# Power.net
KiCad netlist of a schematic drawn in Altium Designer
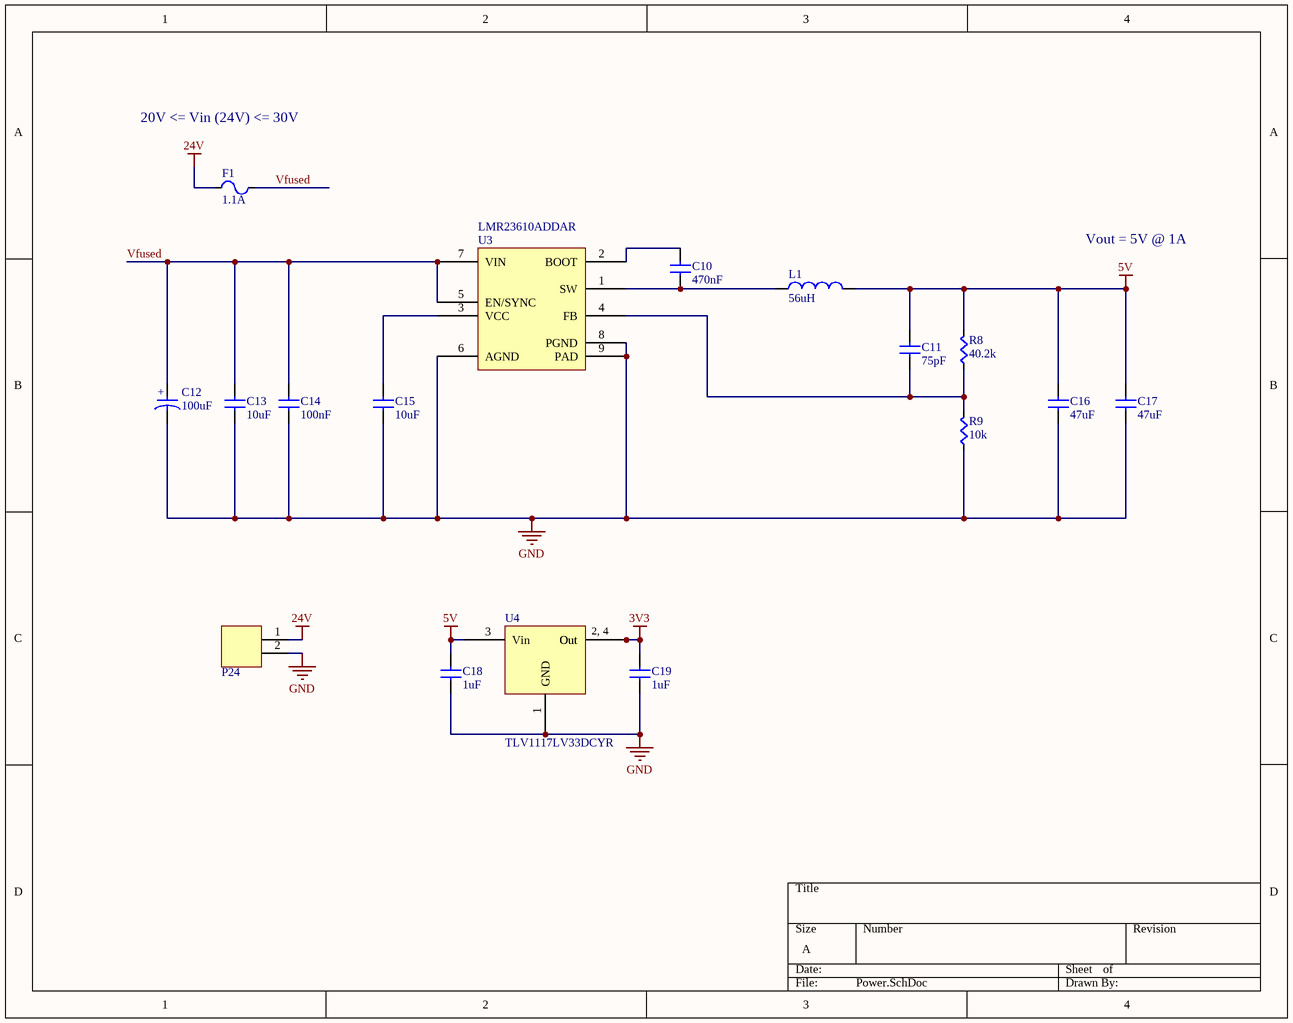
[diagram p0: Power.SchDoc]

(export (version "E")
  (design (tool "Eeschema 10.0.6"))
  (components
    (comp (ref "C10")
      (value "470nF")
      (footprint "CAPC0603")
      (fields (field (name "Comment") "Cap"))
      (libsource (lib "Passives") (part "Cap"))
    )
    (comp (ref "C11")
      (value "75pF")
      (footprint "CAPC0603")
      (fields (field (name "Comment") "Cap"))
      (libsource (lib "Passives") (part "Cap"))
    )
    (comp (ref "C12")
      (value "100uF")
      (footprint "EEHZA1H101P")
      (description "CAP ALUM POLY HYB 100UF 50V SMD")
      (fields (field (name "VOLTAGE") "50V") (field (name "TOLERANCE") "20%"))
      (libsource (lib "SubjuGator8") (part "EEHZA1H101P"))
    )
    (comp (ref "C13")
      (value "10uF")
      (footprint "CAP1210")
      (fields (field (name "Comment") "Cap"))
      (libsource (lib "Passives") (part "Cap"))
    )
    (comp (ref "C14")
      (value "100nF")
      (footprint "CAPC0603")
      (fields (field (name "Comment") "Cap"))
      (libsource (lib "Passives") (part "Cap"))
    )
    (comp (ref "C15")
      (value "10uF")
      (footprint "CAPC0603")
      (fields (field (name "Comment") "Cap"))
      (libsource (lib "Passives") (part "Cap"))
    )
    (comp (ref "C16")
      (value "47uF")
      (footprint "CAP1210")
      (fields (field (name "Comment") "Cap"))
      (libsource (lib "SubjuGator8") (part "Cap"))
    )
    (comp (ref "C17")
      (value "47uF")
      (footprint "CAP1210")
      (fields (field (name "Comment") "Cap"))
      (libsource (lib "SubjuGator8") (part "Cap"))
    )
    (comp (ref "C18")
      (value "1uF")
      (footprint "CAPC0603")
      (fields (field (name "MANUFACTURER PART NUMBER") "C0603C105K8PACTU") (field (name "Comment") "Cap"))
      (libsource (lib "SubjuGator8") (part "Cap"))
    )
    (comp (ref "C19")
      (value "1uF")
      (footprint "CAPC0603")
      (fields (field (name "MANUFACTURER PART NUMBER") "C0603C105K8PACTU") (field (name "Comment") "Cap"))
      (libsource (lib "SubjuGator8") (part "Cap"))
    )
    (comp (ref "F1")
      (value "1.1A")
      (footprint "PTC7451X11N")
      (fields (field (name "Comment") "PTC Fuse"))
      (libsource (lib "SubjuGator8") (part "PTC_Fuse"))
    )
    (comp (ref "L1")
      (value "56uH")
      (footprint "MSS1048-563MLB")
      (description "FIXED IND 56UH 1.7A 126 MOHM")
      (fields (field (name "Comment") "MSS1048-563MLB"))
      (libsource (lib "SubjuGator8") (part "MSS1048-563MLB"))
    )
    (comp (ref "P24")
      (value "2-pin Vert Sherlock")
      (footprint "MOLEX-HDR-1X2-SHERLOCK-VERT")
      (libsource (lib "SubjuGator8") (part "MOLEX-HDR-1x2-SHERLOCK_VERT"))
    )
    (comp (ref "R8")
      (value "40.2k")
      (footprint "RES0603")
      (fields (field (name "Comment") "Res"))
      (libsource (lib "SubjuGator8") (part "Res"))
    )
    (comp (ref "R9")
      (value "10k")
      (footprint "RES0603")
      (fields (field (name "Comment") "Res"))
      (libsource (lib "SubjuGator8") (part "Res"))
    )
    (comp (ref "U3")
      (value "LMR23610ADDAR")
      (footprint "LMR23610ADDAR")
      (description "IC REG BUCK ADJ 1A SYNC 8SOPWRPD")
      (libsource (lib "SubjuGator8") (part "LMR23610ADDAR"))
    )
    (comp (ref "U4")
      (value "TLV1117LV33DCYR")
      (footprint "SOT23-4N")
      (description "IC REG LINEAR 3.3V 1A SOT223-4")
      (fields (field (name "DIGI-KEY PART NUMBER") "296-28778-1-ND"))
      (libsource (lib "ICs") (part "TLV1117LV33DCYR"))
    )
  )
  (nets
    (net (code "1") (name "/Vfused") (class "Default")
      (node (ref "C12") (pin "1") (pinfunction "1_1") (pintype "passive"))
      (node (ref "C13") (pin "1") (pinfunction "A_1") (pintype "passive"))
      (node (ref "C14") (pin "1") (pinfunction "A_1") (pintype "passive"))
      (node (ref "F1") (pin "2") (pinfunction "B_2") (pintype "passive"))
      (node (ref "U3") (pin "5") (pinfunction "EN/SYNC_5") (pintype "passive"))
      (node (ref "U3") (pin "7") (pinfunction "VIN_7") (pintype "passive"))
    )
    (net (code "2") (name "3V3") (class "Default")
      (node (ref "C19") (pin "1") (pinfunction "A_1") (pintype "passive"))
      (node (ref "U4") (pin "2") (pinfunction "Out_2") (pintype "passive"))
      (node (ref "U4") (pin "4") (pinfunction "Out_4") (pintype "passive"))
    )
    (net (code "3") (name "5V") (class "Default")
      (node (ref "C11") (pin "1") (pinfunction "A_1") (pintype "passive"))
      (node (ref "C16") (pin "1") (pinfunction "A_1") (pintype "passive"))
      (node (ref "C17") (pin "1") (pinfunction "A_1") (pintype "passive"))
      (node (ref "C18") (pin "1") (pinfunction "A_1") (pintype "passive"))
      (node (ref "L1") (pin "2") (pinfunction "2_2") (pintype "passive"))
      (node (ref "R8") (pin "1") (pinfunction "A_1") (pintype "passive"))
      (node (ref "U4") (pin "3") (pinfunction "Vin_3") (pintype "passive"))
    )
    (net (code "4") (name "24V") (class "Default")
      (node (ref "F1") (pin "1") (pinfunction "A_1") (pintype "passive"))
      (node (ref "P24") (pin "1") (pinfunction "1_1") (pintype "passive"))
    )
    (net (code "5") (name "GND") (class "Default")
      (node (ref "C12") (pin "2") (pinfunction "2_2") (pintype "passive"))
      (node (ref "C13") (pin "2") (pinfunction "B_2") (pintype "passive"))
      (node (ref "C14") (pin "2") (pinfunction "B_2") (pintype "passive"))
      (node (ref "C15") (pin "2") (pinfunction "B_2") (pintype "passive"))
      (node (ref "C16") (pin "2") (pinfunction "B_2") (pintype "passive"))
      (node (ref "C17") (pin "2") (pinfunction "B_2") (pintype "passive"))
      (node (ref "C18") (pin "2") (pinfunction "B_2") (pintype "passive"))
      (node (ref "C19") (pin "2") (pinfunction "B_2") (pintype "passive"))
      (node (ref "P24") (pin "2") (pinfunction "2_2") (pintype "passive"))
      (node (ref "R9") (pin "2") (pinfunction "B_2") (pintype "passive"))
      (node (ref "U3") (pin "6") (pinfunction "AGND_6") (pintype "passive"))
      (node (ref "U3") (pin "8") (pinfunction "PGND_8") (pintype "passive"))
      (node (ref "U3") (pin "9") (pinfunction "PAD_9") (pintype "passive"))
      (node (ref "U4") (pin "1") (pinfunction "GND_1") (pintype "passive"))
    )
    (net (code "6") (name "Net-(C10-A)") (class "Default")
      (node (ref "C10") (pin "1") (pinfunction "A_1") (pintype "passive"))
      (node (ref "U3") (pin "2") (pinfunction "BOOT_2") (pintype "passive"))
    )
    (net (code "7") (name "Net-(C10-B)") (class "Default")
      (node (ref "C10") (pin "2") (pinfunction "B_2") (pintype "passive"))
      (node (ref "L1") (pin "1") (pinfunction "1_1") (pintype "passive"))
      (node (ref "U3") (pin "1") (pinfunction "SW_1") (pintype "passive"))
    )
    (net (code "8") (name "Net-(C11-B)") (class "Default")
      (node (ref "C11") (pin "2") (pinfunction "B_2") (pintype "passive"))
      (node (ref "R8") (pin "2") (pinfunction "B_2") (pintype "passive"))
      (node (ref "R9") (pin "1") (pinfunction "A_1") (pintype "passive"))
      (node (ref "U3") (pin "4") (pinfunction "FB_4") (pintype "passive"))
    )
    (net (code "9") (name "Net-(C15-A)") (class "Default")
      (node (ref "C15") (pin "1") (pinfunction "A_1") (pintype "passive"))
      (node (ref "U3") (pin "3") (pinfunction "VCC_3") (pintype "passive"))
    )
  )
)
